# Sheet2.net
KiCad netlist of a schematic drawn in Altium Designer
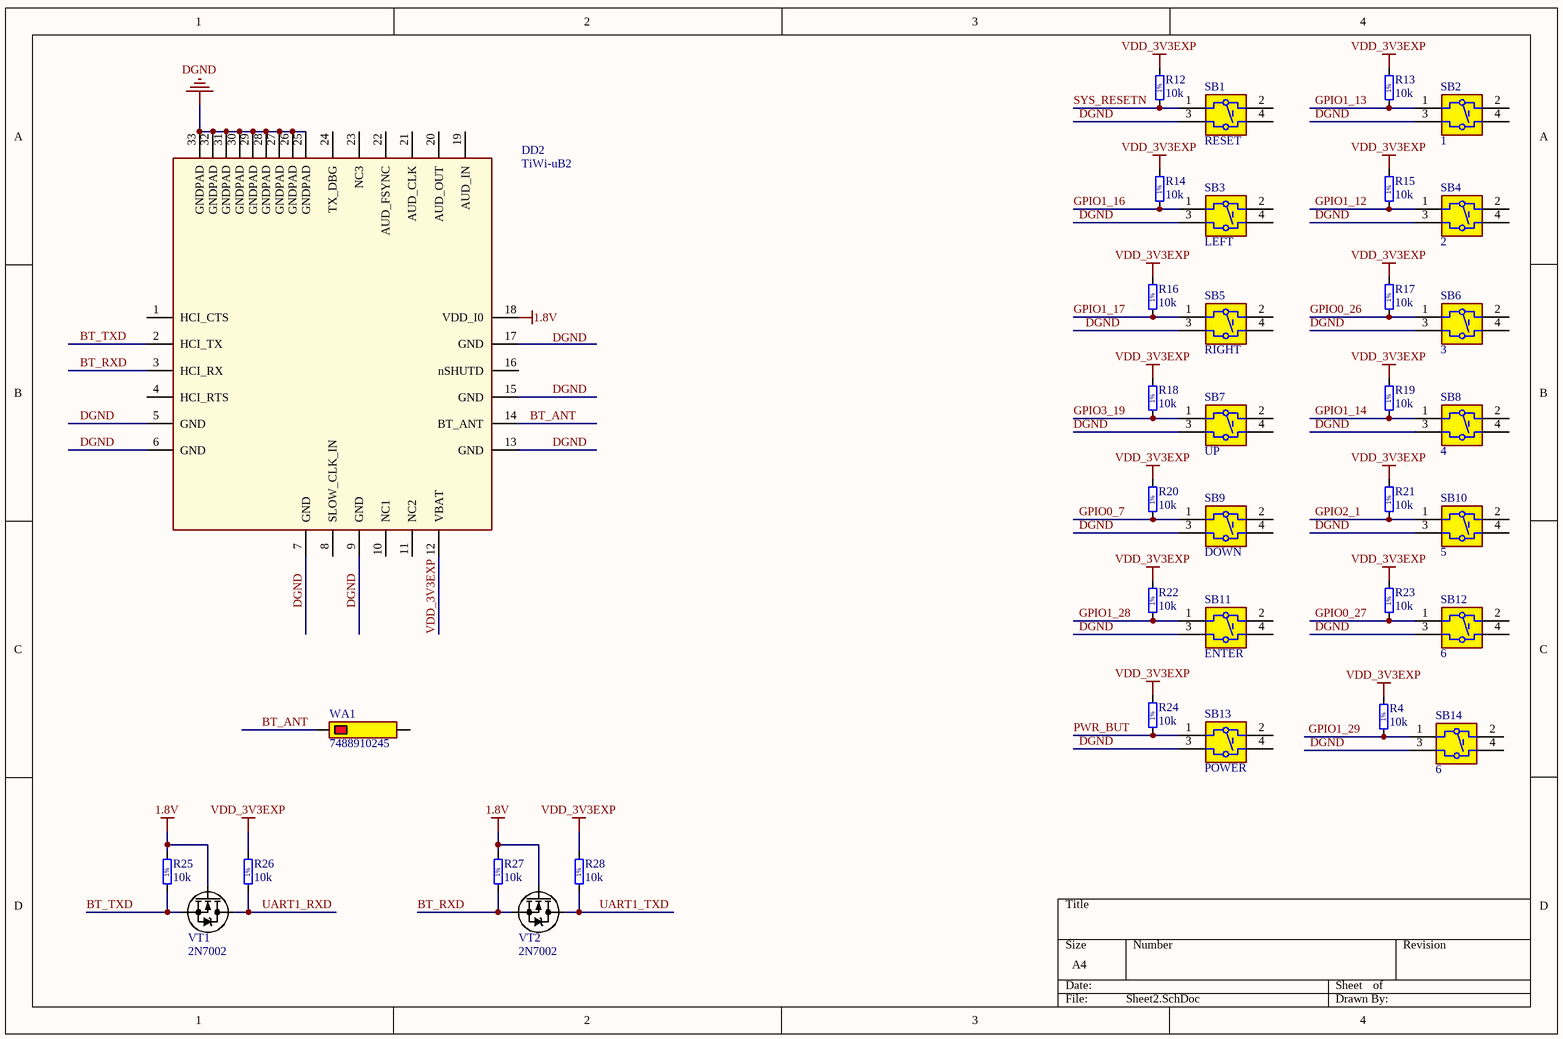
[diagram p0: Sheet2.SchDoc]

(export (version "E")
  (design (tool "Eeschema 10.0.6"))
  (components
    (comp (ref "DD2") (value "TiWi-uB2") (footprint "TiWi-uB2") (libsource (lib "Schlib1") (part "TiWi-uB2")))
    (comp (ref "R4")
      (value "10k")
      (footprint "RES0603R")
      (fields
        (field (name "PART NUMBER") "R0603_10K_1%_0.1W_100PPM")
        (field (name "POWER") "0.1W")
        (field (name "TOLERANCE") "±1%")
        (field (name "AUTHOR") "CERN DEM JLC")
      )
      (libsource (lib "Resistor") (part "Resistor - 1%"))
    )
    (comp (ref "R12")
      (value "10k")
      (footprint "RES0603R")
      (fields
        (field (name "PART NUMBER") "R0603_10K_1%_0.1W_100PPM")
        (field (name "POWER") "0.1W")
        (field (name "TOLERANCE") "±1%")
        (field (name "AUTHOR") "CERN DEM JLC")
      )
      (libsource (lib "Resistor") (part "Resistor - 1%"))
    )
    (comp (ref "R13")
      (value "10k")
      (footprint "RES0603R")
      (fields
        (field (name "PART NUMBER") "R0603_10K_1%_0.1W_100PPM")
        (field (name "POWER") "0.1W")
        (field (name "TOLERANCE") "±1%")
        (field (name "AUTHOR") "CERN DEM JLC")
      )
      (libsource (lib "Resistor") (part "Resistor - 1%"))
    )
    (comp (ref "R14")
      (value "10k")
      (footprint "RES0603R")
      (fields
        (field (name "PART NUMBER") "R0603_10K_1%_0.1W_100PPM")
        (field (name "POWER") "0.1W")
        (field (name "TOLERANCE") "±1%")
        (field (name "AUTHOR") "CERN DEM JLC")
      )
      (libsource (lib "Resistor") (part "Resistor - 1%"))
    )
    (comp (ref "R15")
      (value "10k")
      (footprint "RES0603R")
      (fields
        (field (name "PART NUMBER") "R0603_10K_1%_0.1W_100PPM")
        (field (name "POWER") "0.1W")
        (field (name "TOLERANCE") "±1%")
        (field (name "AUTHOR") "CERN DEM JLC")
      )
      (libsource (lib "Resistor") (part "Resistor - 1%"))
    )
    (comp (ref "R16")
      (value "10k")
      (footprint "RES0603R")
      (fields
        (field (name "PART NUMBER") "R0603_10K_1%_0.1W_100PPM")
        (field (name "POWER") "0.1W")
        (field (name "TOLERANCE") "±1%")
        (field (name "AUTHOR") "CERN DEM JLC")
      )
      (libsource (lib "Resistor") (part "Resistor - 1%"))
    )
    (comp (ref "R17")
      (value "10k")
      (footprint "RES0603R")
      (fields
        (field (name "PART NUMBER") "R0603_10K_1%_0.1W_100PPM")
        (field (name "POWER") "0.1W")
        (field (name "TOLERANCE") "±1%")
        (field (name "AUTHOR") "CERN DEM JLC")
      )
      (libsource (lib "Resistor") (part "Resistor - 1%"))
    )
    (comp (ref "R18")
      (value "10k")
      (footprint "RES0603R")
      (fields
        (field (name "PART NUMBER") "R0603_10K_1%_0.1W_100PPM")
        (field (name "POWER") "0.1W")
        (field (name "TOLERANCE") "±1%")
        (field (name "AUTHOR") "CERN DEM JLC")
      )
      (libsource (lib "Resistor") (part "Resistor - 1%"))
    )
    (comp (ref "R19")
      (value "10k")
      (footprint "RES0603R")
      (fields
        (field (name "PART NUMBER") "R0603_10K_1%_0.1W_100PPM")
        (field (name "POWER") "0.1W")
        (field (name "TOLERANCE") "±1%")
        (field (name "AUTHOR") "CERN DEM JLC")
      )
      (libsource (lib "Resistor") (part "Resistor - 1%"))
    )
    (comp (ref "R20")
      (value "10k")
      (footprint "RES0603R")
      (fields
        (field (name "PART NUMBER") "R0603_10K_1%_0.1W_100PPM")
        (field (name "POWER") "0.1W")
        (field (name "TOLERANCE") "±1%")
        (field (name "AUTHOR") "CERN DEM JLC")
      )
      (libsource (lib "Resistor") (part "Resistor - 1%"))
    )
    (comp (ref "R21")
      (value "10k")
      (footprint "RES0603R")
      (fields
        (field (name "PART NUMBER") "R0603_10K_1%_0.1W_100PPM")
        (field (name "POWER") "0.1W")
        (field (name "TOLERANCE") "±1%")
        (field (name "AUTHOR") "CERN DEM JLC")
      )
      (libsource (lib "Resistor") (part "Resistor - 1%"))
    )
    (comp (ref "R22")
      (value "10k")
      (footprint "RES0603R")
      (fields
        (field (name "PART NUMBER") "R0603_10K_1%_0.1W_100PPM")
        (field (name "POWER") "0.1W")
        (field (name "TOLERANCE") "±1%")
        (field (name "AUTHOR") "CERN DEM JLC")
      )
      (libsource (lib "Resistor") (part "Resistor - 1%"))
    )
    (comp (ref "R23")
      (value "10k")
      (footprint "RES0603R")
      (fields
        (field (name "PART NUMBER") "R0603_10K_1%_0.1W_100PPM")
        (field (name "POWER") "0.1W")
        (field (name "TOLERANCE") "±1%")
        (field (name "AUTHOR") "CERN DEM JLC")
      )
      (libsource (lib "Resistor") (part "Resistor - 1%"))
    )
    (comp (ref "R24")
      (value "10k")
      (footprint "RES0603R")
      (fields
        (field (name "PART NUMBER") "R0603_10K_1%_0.1W_100PPM")
        (field (name "POWER") "0.1W")
        (field (name "TOLERANCE") "±1%")
        (field (name "AUTHOR") "CERN DEM JLC")
      )
      (libsource (lib "Resistor") (part "Resistor - 1%"))
    )
    (comp (ref "R25")
      (value "10k")
      (footprint "RES0603R")
      (fields
        (field (name "PART NUMBER") "R0603_10K_1%_0.1W_100PPM")
        (field (name "POWER") "0.1W")
        (field (name "TOLERANCE") "±1%")
        (field (name "AUTHOR") "CERN DEM JLC")
      )
      (libsource (lib "Resistor") (part "Resistor - 1%"))
    )
    (comp (ref "R26")
      (value "10k")
      (footprint "RES0603R")
      (fields
        (field (name "PART NUMBER") "R0603_10K_1%_0.1W_100PPM")
        (field (name "POWER") "0.1W")
        (field (name "TOLERANCE") "±1%")
        (field (name "AUTHOR") "CERN DEM JLC")
      )
      (libsource (lib "Resistor") (part "Resistor - 1%"))
    )
    (comp (ref "R27")
      (value "10k")
      (footprint "RES0603R")
      (fields
        (field (name "PART NUMBER") "R0603_10K_1%_0.1W_100PPM")
        (field (name "POWER") "0.1W")
        (field (name "TOLERANCE") "±1%")
        (field (name "AUTHOR") "CERN DEM JLC")
      )
      (libsource (lib "Resistor") (part "Resistor - 1%"))
    )
    (comp (ref "R28")
      (value "10k")
      (footprint "RES0603R")
      (fields
        (field (name "PART NUMBER") "R0603_10K_1%_0.1W_100PPM")
        (field (name "POWER") "0.1W")
        (field (name "TOLERANCE") "±1%")
        (field (name "AUTHOR") "CERN DEM JLC")
      )
      (libsource (lib "Resistor") (part "Resistor - 1%"))
    )
    (comp (ref "SB1")
      (value "RESET")
      (footprint "DTSMW-3.8N")
      (fields (field (name "PART NUMBER") "DTSMW-3.8N"))
      (libsource (lib "Button") (part "TACT_4P_2W"))
    )
    (comp (ref "SB2")
      (value "1")
      (footprint "DTSMW-3.8N")
      (fields (field (name "PART NUMBER") "DTSMW-3.8N"))
      (libsource (lib "Button") (part "TACT_4P_2W"))
    )
    (comp (ref "SB3")
      (value "LEFT")
      (footprint "DTSMW-3.8N")
      (fields (field (name "PART NUMBER") "DTSMW-3.8N"))
      (libsource (lib "Button") (part "TACT_4P_2W"))
    )
    (comp (ref "SB4")
      (value "2")
      (footprint "DTSMW-3.8N")
      (fields (field (name "PART NUMBER") "DTSMW-3.8N"))
      (libsource (lib "Button") (part "TACT_4P_2W"))
    )
    (comp (ref "SB5")
      (value "RIGHT")
      (footprint "DTSMW-3.8N")
      (fields (field (name "PART NUMBER") "DTSMW-3.8N"))
      (libsource (lib "Button") (part "TACT_4P_2W"))
    )
    (comp (ref "SB6")
      (value "3")
      (footprint "DTSMW-3.8N")
      (fields (field (name "PART NUMBER") "DTSMW-3.8N"))
      (libsource (lib "Button") (part "TACT_4P_2W"))
    )
    (comp (ref "SB7")
      (value "UP")
      (footprint "DTSMW-3.8N")
      (fields (field (name "PART NUMBER") "DTSMW-3.8N"))
      (libsource (lib "Button") (part "TACT_4P_2W"))
    )
    (comp (ref "SB8")
      (value "4")
      (footprint "DTSMW-3.8N")
      (fields (field (name "PART NUMBER") "DTSMW-3.8N"))
      (libsource (lib "Button") (part "TACT_4P_2W"))
    )
    (comp (ref "SB9")
      (value "DOWN")
      (footprint "DTSMW-3.8N")
      (fields (field (name "PART NUMBER") "DTSMW-3.8N"))
      (libsource (lib "Button") (part "TACT_4P_2W"))
    )
    (comp (ref "SB10")
      (value "5")
      (footprint "DTSMW-3.8N")
      (fields (field (name "PART NUMBER") "DTSMW-3.8N"))
      (libsource (lib "Button") (part "TACT_4P_2W"))
    )
    (comp (ref "SB11")
      (value "ENTER")
      (footprint "DTSMW-3.8N")
      (fields (field (name "PART NUMBER") "DTSMW-3.8N"))
      (libsource (lib "Button") (part "TACT_4P_2W"))
    )
    (comp (ref "SB12")
      (value "6")
      (footprint "DTSMW-3.8N")
      (fields (field (name "PART NUMBER") "DTSMW-3.8N"))
      (libsource (lib "Button") (part "TACT_4P_2W"))
    )
    (comp (ref "SB13")
      (value "POWER")
      (footprint "DTSMW-3.8N")
      (fields (field (name "PART NUMBER") "DTSMW-3.8N"))
      (libsource (lib "Button") (part "TACT_4P_2W"))
    )
    (comp (ref "SB14")
      (value "6")
      (footprint "DTSMW-3.8N")
      (fields (field (name "PART NUMBER") "DTSMW-3.8N"))
      (libsource (lib "Button") (part "TACT_4P_2W"))
    )
    (comp (ref "VT1")
      (value "2N7002")
      (footprint "SOT23")
      (description "N-Channel Enhancement Mode FET")
      (fields (field (name "AUTHOR") "I. Kuznetsov"))
      (libsource (lib "IC And Semiconductor") (part "N_CH_MOSFET"))
    )
    (comp (ref "VT2")
      (value "2N7002")
      (footprint "SOT23")
      (description "N-Channel Enhancement Mode FET")
      (fields (field (name "AUTHOR") "I. Kuznetsov"))
      (libsource (lib "IC And Semiconductor") (part "N_CH_MOSFET"))
    )
    (comp (ref "WA1")
      (value "7488910245")
      (footprint "7488910245")
      (description "Bluetooth Antenna")
      (fields (field (name "MANUFACTURER") "Wurth Elektronik") (field (name "AUTHOR") "I. Kuznetsov"))
      (libsource (lib "Antenna") (part "7488910245"))
    )
  )
  (nets
    (net (code "1") (name "/BT_ANT") (class "Default")
      (node (ref "DD2") (pin "14") (pinfunction "BT_ANT_14") (pintype "passive"))
      (node (ref "WA1") (pin "1") (pinfunction "1_1") (pintype "passive"))
    )
    (net (code "2") (name "/BT_RXD") (class "Default")
      (node (ref "DD2") (pin "3") (pinfunction "HCI_RX_3") (pintype "passive"))
      (node (ref "R27") (pin "1") (pinfunction "1_1") (pintype "passive"))
      (node (ref "VT2") (pin "2") (pinfunction "S_2") (pintype "passive"))
    )
    (net (code "3") (name "/BT_TXD") (class "Default")
      (node (ref "DD2") (pin "2") (pinfunction "HCI_TX_2") (pintype "passive"))
      (node (ref "R25") (pin "1") (pinfunction "1_1") (pintype "passive"))
      (node (ref "VT1") (pin "2") (pinfunction "S_2") (pintype "passive"))
    )
    (net (code "4") (name "/GPIO0_7") (class "Default")
      (node (ref "R20") (pin "1") (pinfunction "1_1") (pintype "passive"))
      (node (ref "SB9") (pin "1") (pinfunction "T1_1") (pintype "passive"))
    )
    (net (code "5") (name "/GPIO0_26") (class "Default")
      (node (ref "R17") (pin "1") (pinfunction "1_1") (pintype "passive"))
      (node (ref "SB6") (pin "1") (pinfunction "T1_1") (pintype "passive"))
    )
    (net (code "6") (name "/GPIO0_27") (class "Default")
      (node (ref "R23") (pin "1") (pinfunction "1_1") (pintype "passive"))
      (node (ref "SB12") (pin "1") (pinfunction "T1_1") (pintype "passive"))
    )
    (net (code "7") (name "/GPIO1_12") (class "Default")
      (node (ref "R15") (pin "1") (pinfunction "1_1") (pintype "passive"))
      (node (ref "SB4") (pin "1") (pinfunction "T1_1") (pintype "passive"))
    )
    (net (code "8") (name "/GPIO1_13") (class "Default")
      (node (ref "R13") (pin "1") (pinfunction "1_1") (pintype "passive"))
      (node (ref "SB2") (pin "1") (pinfunction "T1_1") (pintype "passive"))
    )
    (net (code "9") (name "/GPIO1_14") (class "Default")
      (node (ref "R19") (pin "1") (pinfunction "1_1") (pintype "passive"))
      (node (ref "SB8") (pin "1") (pinfunction "T1_1") (pintype "passive"))
    )
    (net (code "10") (name "/GPIO1_16") (class "Default")
      (node (ref "R14") (pin "1") (pinfunction "1_1") (pintype "passive"))
      (node (ref "SB3") (pin "1") (pinfunction "T1_1") (pintype "passive"))
    )
    (net (code "11") (name "/GPIO1_17") (class "Default")
      (node (ref "R16") (pin "1") (pinfunction "1_1") (pintype "passive"))
      (node (ref "SB5") (pin "1") (pinfunction "T1_1") (pintype "passive"))
    )
    (net (code "12") (name "/GPIO1_28") (class "Default")
      (node (ref "R22") (pin "1") (pinfunction "1_1") (pintype "passive"))
      (node (ref "SB11") (pin "1") (pinfunction "T1_1") (pintype "passive"))
    )
    (net (code "13") (name "/GPIO1_29") (class "Default")
      (node (ref "R4") (pin "1") (pinfunction "1_1") (pintype "passive"))
      (node (ref "SB14") (pin "1") (pinfunction "T1_1") (pintype "passive"))
    )
    (net (code "14") (name "/GPIO2_1") (class "Default")
      (node (ref "R21") (pin "1") (pinfunction "1_1") (pintype "passive"))
      (node (ref "SB10") (pin "1") (pinfunction "T1_1") (pintype "passive"))
    )
    (net (code "15") (name "/GPIO3_19") (class "Default")
      (node (ref "R18") (pin "1") (pinfunction "1_1") (pintype "passive"))
      (node (ref "SB7") (pin "1") (pinfunction "T1_1") (pintype "passive"))
    )
    (net (code "16") (name "/PWR_BUT") (class "Default")
      (node (ref "R24") (pin "1") (pinfunction "1_1") (pintype "passive"))
      (node (ref "SB13") (pin "1") (pinfunction "T1_1") (pintype "passive"))
    )
    (net (code "17") (name "/SYS_RESETN") (class "Default")
      (node (ref "R12") (pin "1") (pinfunction "1_1") (pintype "passive"))
      (node (ref "SB1") (pin "1") (pinfunction "T1_1") (pintype "passive"))
    )
    (net (code "18") (name "/UART1_RXD") (class "Default")
      (node (ref "R26") (pin "1") (pinfunction "1_1") (pintype "passive"))
      (node (ref "VT1") (pin "3") (pinfunction "D_3") (pintype "passive"))
    )
    (net (code "19") (name "/UART1_TXD") (class "Default")
      (node (ref "R28") (pin "1") (pinfunction "1_1") (pintype "passive"))
      (node (ref "VT2") (pin "3") (pinfunction "D_3") (pintype "passive"))
    )
    (net (code "20") (name "1.8V") (class "Default")
      (node (ref "DD2") (pin "18") (pinfunction "VDD_I0_18") (pintype "passive"))
      (node (ref "R25") (pin "2") (pinfunction "2_2") (pintype "passive"))
      (node (ref "R27") (pin "2") (pinfunction "2_2") (pintype "passive"))
      (node (ref "VT1") (pin "1") (pinfunction "G_1") (pintype "passive"))
      (node (ref "VT2") (pin "1") (pinfunction "G_1") (pintype "passive"))
    )
    (net (code "21") (name "DGND") (class "Default")
      (node (ref "DD2") (pin "13") (pinfunction "GND_13") (pintype "passive"))
      (node (ref "DD2") (pin "15") (pinfunction "GND_15") (pintype "passive"))
      (node (ref "DD2") (pin "25") (pinfunction "GNDPAD_25") (pintype "passive"))
      (node (ref "DD2") (pin "26") (pinfunction "GNDPAD_26") (pintype "passive"))
      (node (ref "DD2") (pin "27") (pinfunction "GNDPAD_27") (pintype "passive"))
      (node (ref "DD2") (pin "28") (pinfunction "GNDPAD_28") (pintype "passive"))
      (node (ref "DD2") (pin "29") (pinfunction "GNDPAD_29") (pintype "passive"))
      (node (ref "DD2") (pin "30") (pinfunction "GNDPAD_30") (pintype "passive"))
      (node (ref "DD2") (pin "31") (pinfunction "GNDPAD_31") (pintype "passive"))
      (node (ref "DD2") (pin "32") (pinfunction "GNDPAD_32") (pintype "passive"))
      (node (ref "DD2") (pin "33") (pinfunction "GNDPAD_33") (pintype "passive"))
      (node (ref "DD2") (pin "5") (pinfunction "GND_5") (pintype "passive"))
      (node (ref "DD2") (pin "6") (pinfunction "GND_6") (pintype "passive"))
      (node (ref "DD2") (pin "7") (pinfunction "GND_7") (pintype "passive"))
      (node (ref "DD2") (pin "9") (pinfunction "GND_9") (pintype "passive"))
      (node (ref "SB1") (pin "3") (pinfunction "T3_3") (pintype "passive"))
      (node (ref "SB10") (pin "3") (pinfunction "T3_3") (pintype "passive"))
      (node (ref "SB11") (pin "3") (pinfunction "T3_3") (pintype "passive"))
      (node (ref "SB12") (pin "3") (pinfunction "T3_3") (pintype "passive"))
      (node (ref "SB13") (pin "3") (pinfunction "T3_3") (pintype "passive"))
      (node (ref "SB14") (pin "3") (pinfunction "T3_3") (pintype "passive"))
      (node (ref "SB2") (pin "3") (pinfunction "T3_3") (pintype "passive"))
      (node (ref "SB3") (pin "3") (pinfunction "T3_3") (pintype "passive"))
      (node (ref "SB4") (pin "3") (pinfunction "T3_3") (pintype "passive"))
      (node (ref "SB5") (pin "3") (pinfunction "T3_3") (pintype "passive"))
      (node (ref "SB6") (pin "3") (pinfunction "T3_3") (pintype "passive"))
      (node (ref "SB7") (pin "3") (pinfunction "T3_3") (pintype "passive"))
      (node (ref "SB8") (pin "3") (pinfunction "T3_3") (pintype "passive"))
      (node (ref "SB9") (pin "3") (pinfunction "T3_3") (pintype "passive"))
    )
    (net (code "22") (name "VDD_3V3EXP") (class "Default")
      (node (ref "DD2") (pin "12") (pinfunction "VBAT_12") (pintype "passive"))
      (node (ref "R12") (pin "2") (pinfunction "2_2") (pintype "passive"))
      (node (ref "R13") (pin "2") (pinfunction "2_2") (pintype "passive"))
      (node (ref "R14") (pin "2") (pinfunction "2_2") (pintype "passive"))
      (node (ref "R15") (pin "2") (pinfunction "2_2") (pintype "passive"))
      (node (ref "R16") (pin "2") (pinfunction "2_2") (pintype "passive"))
      (node (ref "R17") (pin "2") (pinfunction "2_2") (pintype "passive"))
      (node (ref "R18") (pin "2") (pinfunction "2_2") (pintype "passive"))
      (node (ref "R19") (pin "2") (pinfunction "2_2") (pintype "passive"))
      (node (ref "R20") (pin "2") (pinfunction "2_2") (pintype "passive"))
      (node (ref "R21") (pin "2") (pinfunction "2_2") (pintype "passive"))
      (node (ref "R22") (pin "2") (pinfunction "2_2") (pintype "passive"))
      (node (ref "R23") (pin "2") (pinfunction "2_2") (pintype "passive"))
      (node (ref "R24") (pin "2") (pinfunction "2_2") (pintype "passive"))
      (node (ref "R26") (pin "2") (pinfunction "2_2") (pintype "passive"))
      (node (ref "R28") (pin "2") (pinfunction "2_2") (pintype "passive"))
      (node (ref "R4") (pin "2") (pinfunction "2_2") (pintype "passive"))
    )
    (net (code "23") (name "unconnected-(DD2-AUD_CLK-Pad21)") (class "Default")
      (node (ref "DD2") (pin "21") (pinfunction "AUD_CLK_21") (pintype "passive"))
    )
    (net (code "24") (name "unconnected-(DD2-AUD_FSYNC-Pad22)") (class "Default")
      (node (ref "DD2") (pin "22") (pinfunction "AUD_FSYNC_22") (pintype "passive"))
    )
    (net (code "25") (name "unconnected-(DD2-AUD_IN-Pad19)") (class "Default")
      (node (ref "DD2") (pin "19") (pinfunction "AUD_IN_19") (pintype "passive"))
    )
    (net (code "26") (name "unconnected-(DD2-AUD_OUT-Pad20)") (class "Default")
      (node (ref "DD2") (pin "20") (pinfunction "AUD_OUT_20") (pintype "passive"))
    )
    (net (code "27") (name "unconnected-(DD2-GND-Pad17)") (class "Default")
      (node (ref "DD2") (pin "17") (pinfunction "GND_17") (pintype "passive"))
    )
    (net (code "28") (name "unconnected-(DD2-HCI_CTS-Pad1)") (class "Default")
      (node (ref "DD2") (pin "1") (pinfunction "HCI_CTS_1") (pintype "passive"))
    )
    (net (code "29") (name "unconnected-(DD2-HCI_RTS-Pad4)") (class "Default")
      (node (ref "DD2") (pin "4") (pinfunction "HCI_RTS_4") (pintype "passive"))
    )
    (net (code "30") (name "unconnected-(DD2-NC1-Pad10)") (class "Default")
      (node (ref "DD2") (pin "10") (pinfunction "NC1_10") (pintype "passive"))
    )
    (net (code "31") (name "unconnected-(DD2-NC2-Pad11)") (class "Default")
      (node (ref "DD2") (pin "11") (pinfunction "NC2_11") (pintype "passive"))
    )
    (net (code "32") (name "unconnected-(DD2-NC3-Pad23)") (class "Default")
      (node (ref "DD2") (pin "23") (pinfunction "NC3_23") (pintype "passive"))
    )
    (net (code "33") (name "unconnected-(DD2-SLOW_CLK_IN-Pad8)") (class "Default")
      (node (ref "DD2") (pin "8") (pinfunction "SLOW_CLK_IN_8") (pintype "passive"))
    )
    (net (code "34") (name "unconnected-(DD2-TX_DBG-Pad24)") (class "Default")
      (node (ref "DD2") (pin "24") (pinfunction "TX_DBG_24") (pintype "passive"))
    )
    (net (code "35") (name "unconnected-(DD2-nSHUTD-Pad16)") (class "Default")
      (node (ref "DD2") (pin "16") (pinfunction "nSHUTD_16") (pintype "passive"))
    )
    (net (code "36") (name "unconnected-(SB1-T2-Pad2)") (class "Default")
      (node (ref "SB1") (pin "2") (pinfunction "T2_2") (pintype "passive"))
    )
    (net (code "37") (name "unconnected-(SB1-T3-Pad4)") (class "Default")
      (node (ref "SB1") (pin "4") (pinfunction "T3_4") (pintype "passive"))
    )
    (net (code "38") (name "unconnected-(SB2-T2-Pad2)") (class "Default")
      (node (ref "SB2") (pin "2") (pinfunction "T2_2") (pintype "passive"))
    )
    (net (code "39") (name "unconnected-(SB2-T3-Pad4)") (class "Default")
      (node (ref "SB2") (pin "4") (pinfunction "T3_4") (pintype "passive"))
    )
    (net (code "40") (name "unconnected-(SB3-T2-Pad2)") (class "Default")
      (node (ref "SB3") (pin "2") (pinfunction "T2_2") (pintype "passive"))
    )
    (net (code "41") (name "unconnected-(SB3-T3-Pad4)") (class "Default")
      (node (ref "SB3") (pin "4") (pinfunction "T3_4") (pintype "passive"))
    )
    (net (code "42") (name "unconnected-(SB4-T2-Pad2)") (class "Default")
      (node (ref "SB4") (pin "2") (pinfunction "T2_2") (pintype "passive"))
    )
    (net (code "43") (name "unconnected-(SB4-T3-Pad4)") (class "Default")
      (node (ref "SB4") (pin "4") (pinfunction "T3_4") (pintype "passive"))
    )
    (net (code "44") (name "unconnected-(SB5-T2-Pad2)") (class "Default")
      (node (ref "SB5") (pin "2") (pinfunction "T2_2") (pintype "passive"))
    )
    (net (code "45") (name "unconnected-(SB5-T3-Pad4)") (class "Default")
      (node (ref "SB5") (pin "4") (pinfunction "T3_4") (pintype "passive"))
    )
    (net (code "46") (name "unconnected-(SB6-T2-Pad2)") (class "Default")
      (node (ref "SB6") (pin "2") (pinfunction "T2_2") (pintype "passive"))
    )
    (net (code "47") (name "unconnected-(SB6-T3-Pad4)") (class "Default")
      (node (ref "SB6") (pin "4") (pinfunction "T3_4") (pintype "passive"))
    )
    (net (code "48") (name "unconnected-(SB7-T2-Pad2)") (class "Default")
      (node (ref "SB7") (pin "2") (pinfunction "T2_2") (pintype "passive"))
    )
    (net (code "49") (name "unconnected-(SB7-T3-Pad4)") (class "Default")
      (node (ref "SB7") (pin "4") (pinfunction "T3_4") (pintype "passive"))
    )
    (net (code "50") (name "unconnected-(SB8-T2-Pad2)") (class "Default")
      (node (ref "SB8") (pin "2") (pinfunction "T2_2") (pintype "passive"))
    )
    (net (code "51") (name "unconnected-(SB8-T3-Pad4)") (class "Default")
      (node (ref "SB8") (pin "4") (pinfunction "T3_4") (pintype "passive"))
    )
    (net (code "52") (name "unconnected-(SB9-T2-Pad2)") (class "Default")
      (node (ref "SB9") (pin "2") (pinfunction "T2_2") (pintype "passive"))
    )
    (net (code "53") (name "unconnected-(SB9-T3-Pad4)") (class "Default")
      (node (ref "SB9") (pin "4") (pinfunction "T3_4") (pintype "passive"))
    )
    (net (code "54") (name "unconnected-(SB10-T2-Pad2)") (class "Default")
      (node (ref "SB10") (pin "2") (pinfunction "T2_2") (pintype "passive"))
    )
    (net (code "55") (name "unconnected-(SB10-T3-Pad4)") (class "Default")
      (node (ref "SB10") (pin "4") (pinfunction "T3_4") (pintype "passive"))
    )
    (net (code "56") (name "unconnected-(SB11-T2-Pad2)") (class "Default")
      (node (ref "SB11") (pin "2") (pinfunction "T2_2") (pintype "passive"))
    )
    (net (code "57") (name "unconnected-(SB11-T3-Pad4)") (class "Default")
      (node (ref "SB11") (pin "4") (pinfunction "T3_4") (pintype "passive"))
    )
    (net (code "58") (name "unconnected-(SB12-T2-Pad2)") (class "Default")
      (node (ref "SB12") (pin "2") (pinfunction "T2_2") (pintype "passive"))
    )
    (net (code "59") (name "unconnected-(SB12-T3-Pad4)") (class "Default")
      (node (ref "SB12") (pin "4") (pinfunction "T3_4") (pintype "passive"))
    )
    (net (code "60") (name "unconnected-(SB13-T2-Pad2)") (class "Default")
      (node (ref "SB13") (pin "2") (pinfunction "T2_2") (pintype "passive"))
    )
    (net (code "61") (name "unconnected-(SB13-T3-Pad4)") (class "Default")
      (node (ref "SB13") (pin "4") (pinfunction "T3_4") (pintype "passive"))
    )
    (net (code "62") (name "unconnected-(SB14-T2-Pad2)") (class "Default")
      (node (ref "SB14") (pin "2") (pinfunction "T2_2") (pintype "passive"))
    )
    (net (code "63") (name "unconnected-(SB14-T3-Pad4)") (class "Default")
      (node (ref "SB14") (pin "4") (pinfunction "T3_4") (pintype "passive"))
    )
    (net (code "64") (name "unconnected-(WA1-Pad2)") (class "Default")
      (node (ref "WA1") (pin "2") (pinfunction "2_2") (pintype "passive"))
    )
  )
)
